# main.net
KiCad netlist of a schematic drawn in Altium Designer
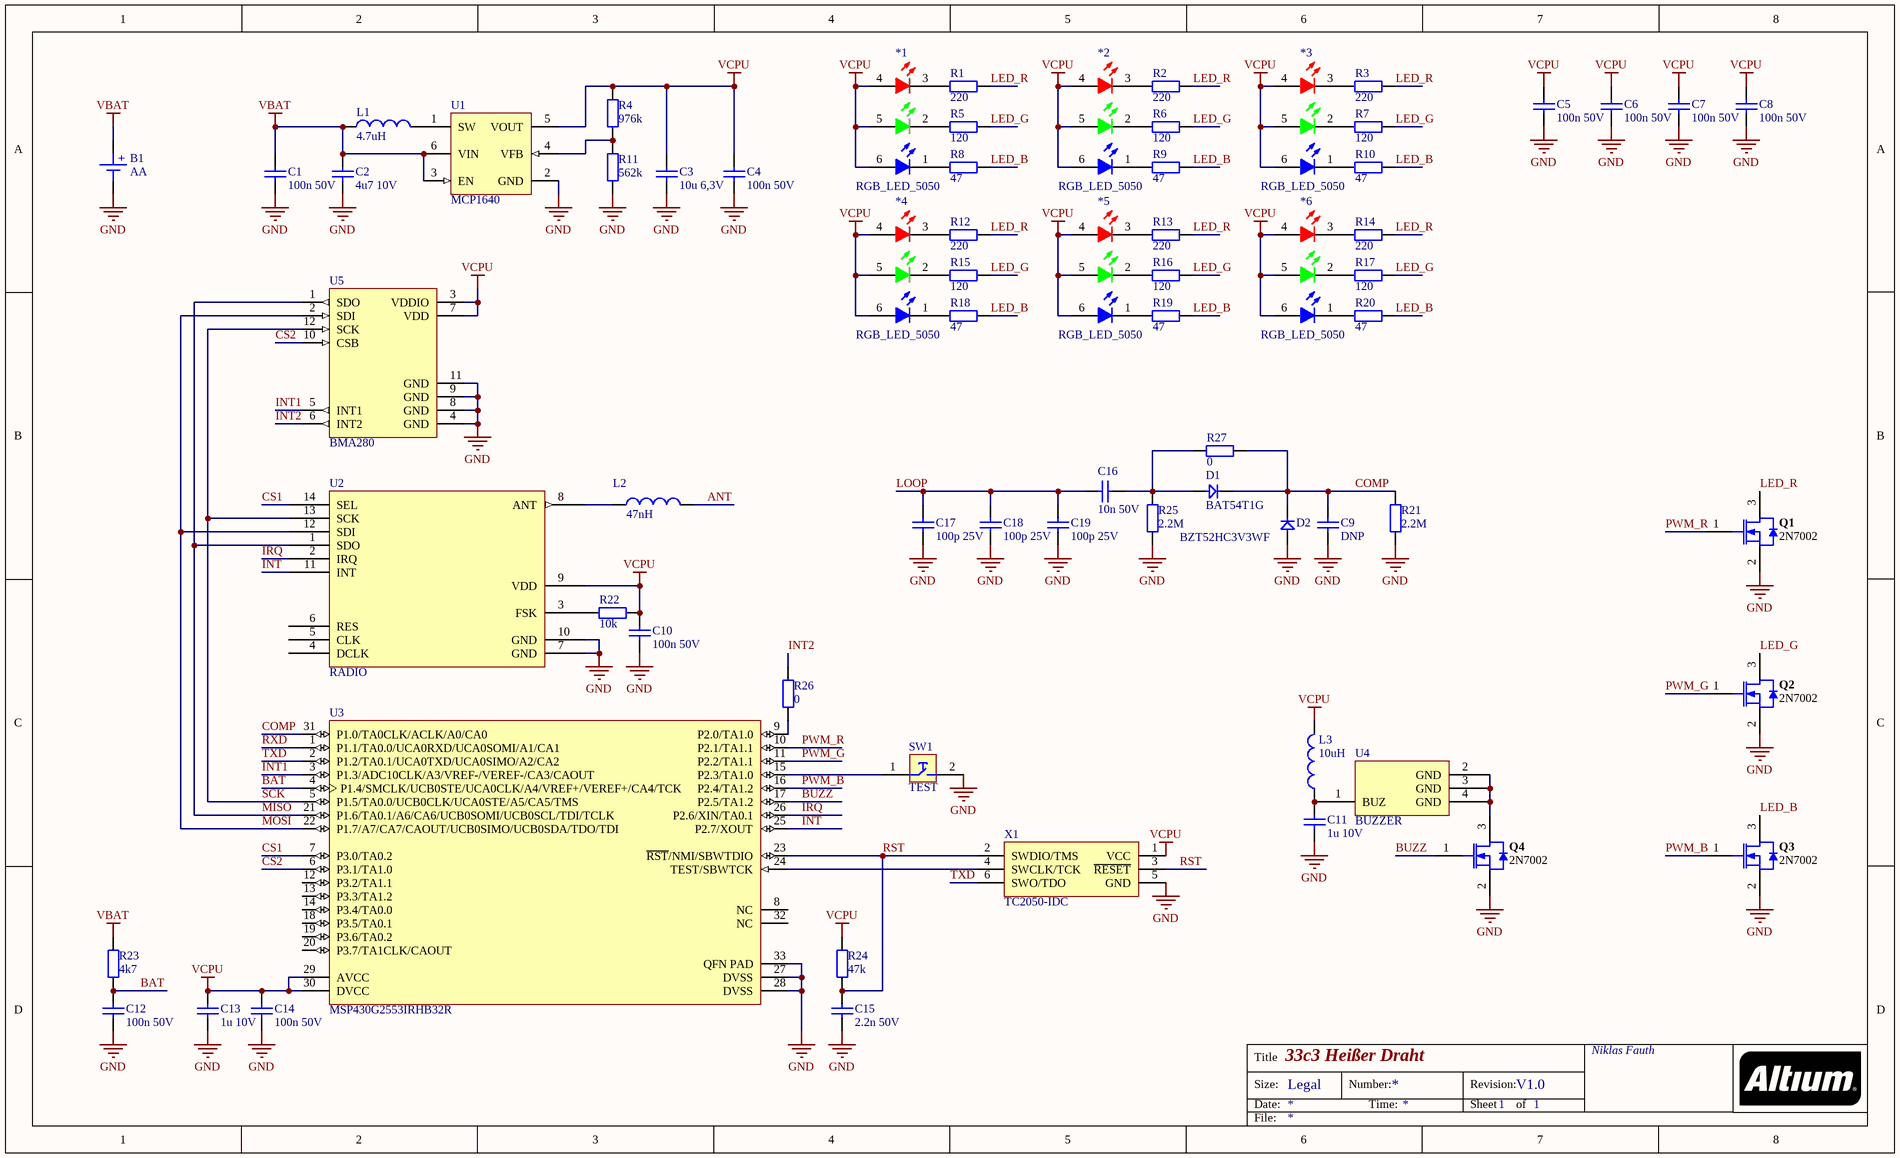
[diagram p0: main.SchDoc]

(export (version "E")
  (design (tool "Eeschema 10.0.6"))
  (components
    (comp (ref "*1")
      (value "RGB_LED_5050")
      (footprint "plcc6")
      (libsource (lib "advanced") (part "RGB_LED_5050"))
    )
    (comp (ref "*2")
      (value "RGB_LED_5050")
      (footprint "plcc6")
      (libsource (lib "advanced") (part "RGB_LED_5050"))
    )
    (comp (ref "*3")
      (value "RGB_LED_5050")
      (footprint "plcc6")
      (libsource (lib "advanced") (part "RGB_LED_5050"))
    )
    (comp (ref "*4")
      (value "RGB_LED_5050")
      (footprint "plcc6")
      (libsource (lib "advanced") (part "RGB_LED_5050"))
    )
    (comp (ref "*5")
      (value "RGB_LED_5050")
      (footprint "plcc6")
      (libsource (lib "advanced") (part "RGB_LED_5050"))
    )
    (comp (ref "*6")
      (value "RGB_LED_5050")
      (footprint "plcc6")
      (libsource (lib "advanced") (part "RGB_LED_5050"))
    )
    (comp (ref "B1")
      (value "AA")
      (footprint "AA-HOLDER")
      (description "Batt Holder AA")
      (libsource (lib "advanced") (part "AA-Batt-Holder"))
    )
    (comp (ref "C1")
      (value "100n 50V")
      (footprint "C-0603-M")
      (description "Capacitor 100n 50V")
      (libsource (lib "Passives") (part "C-0603-100n-50V"))
    )
    (comp (ref "C2")
      (value "4u7 10V")
      (footprint "C-0603-H")
      (description "Capacitor 4.7uF 10V")
      (libsource (lib "Passives") (part "C-0603-4u7-10V"))
    )
    (comp (ref "C3")
      (value "10u 6,3V")
      (footprint "C-0603-H")
      (description "Capacitor 10uF 6,3V")
      (libsource (lib "Passives") (part "C-0603-10u-6,3V"))
    )
    (comp (ref "C4")
      (value "100n 50V")
      (footprint "C-0603-M")
      (description "Capacitor 100n 50V")
      (libsource (lib "Passives") (part "C-0603-100n-50V"))
    )
    (comp (ref "C5")
      (value "100n 50V")
      (footprint "C-0603-M")
      (description "Capacitor 100n 50V")
      (libsource (lib "Passives") (part "C-0603-100n-50V"))
    )
    (comp (ref "C6")
      (value "100n 50V")
      (footprint "C-0603-M")
      (description "Capacitor 100n 50V")
      (libsource (lib "Passives") (part "C-0603-100n-50V"))
    )
    (comp (ref "C7")
      (value "100n 50V")
      (footprint "C-0603-M")
      (description "Capacitor 100n 50V")
      (libsource (lib "Passives") (part "C-0603-100n-50V"))
    )
    (comp (ref "C8")
      (value "100n 50V")
      (footprint "C-0603-M")
      (description "Capacitor 100n 50V")
      (libsource (lib "Passives") (part "C-0603-100n-50V"))
    )
    (comp (ref "C9")
      (value "DNP")
      (footprint "C-0603-H")
      (description "Capacitor 10nF 50V")
      (libsource (lib "Passives") (part "C-0603-10n-50V"))
    )
    (comp (ref "C10")
      (value "100n 50V")
      (footprint "C-0603-M")
      (description "Capacitor 100n 50V")
      (libsource (lib "Passives") (part "C-0603-100n-50V"))
    )
    (comp (ref "C11")
      (value "1u 10V")
      (footprint "C-0603-H")
      (description "Capacitor 1uF 10V")
      (libsource (lib "Passives") (part "C-0603-1u-10V"))
    )
    (comp (ref "C12")
      (value "100n 50V")
      (footprint "C-0603-M")
      (description "Capacitor 100n 50V")
      (libsource (lib "Passives") (part "C-0603-100n-50V"))
    )
    (comp (ref "C13")
      (value "1u 10V")
      (footprint "C-0603-H")
      (description "Capacitor 1uF 10V")
      (libsource (lib "Passives") (part "C-0603-1u-10V"))
    )
    (comp (ref "C14")
      (value "100n 50V")
      (footprint "C-0603-M")
      (description "Capacitor 100n 50V")
      (libsource (lib "Passives") (part "C-0603-100n-50V"))
    )
    (comp (ref "C15")
      (value "2.2n 50V")
      (footprint "C-0603-H")
      (description "Capacitor 2.2n 50V")
      (libsource (lib "Passives") (part "C-0603-2n2-50V"))
    )
    (comp (ref "C16")
      (value "10n 50V")
      (footprint "C-0603-H")
      (description "Capacitor 10nF 50V")
      (libsource (lib "Passives") (part "C-0603-10n-50V"))
    )
    (comp (ref "C17")
      (value "100p 25V")
      (footprint "C-0603-M")
      (description "Capacitor 100pF 25V")
      (libsource (lib "Passives") (part "C-0603-100p-25V"))
    )
    (comp (ref "C18")
      (value "100p 25V")
      (footprint "C-0603-M")
      (description "Capacitor 100pF 25V")
      (libsource (lib "Passives") (part "C-0603-100p-25V"))
    )
    (comp (ref "C19")
      (value "100p 25V")
      (footprint "C-0603-M")
      (description "Capacitor 100pF 25V")
      (libsource (lib "Passives") (part "C-0603-100p-25V"))
    )
    (comp (ref "D1") (value "BAT54T1G") (footprint "SOD123") (libsource (lib "advanced") (part "BAT54T1G")))
    (comp (ref "D2")
      (value "BZT52HC3V3WF")
      (footprint "SOD123")
      (description "BAT54T1G")
      (libsource (lib "advanced") (part "BAT54T1G"))
    )
    (comp (ref "L1")
      (value "4.7uH")
      (footprint "SRN4012")
      (description "SRN4012TA-4R7M")
      (libsource (lib "advanced") (part "L-SRN4012TA-4R7M"))
    )
    (comp (ref "L2") (value "47nH") (footprint "C-0603-M") (libsource (lib "advanced") (part "L-0603-47nH")))
    (comp (ref "L3")
      (value "10uH")
      (footprint "R-0805")
      (description "L 0805 10uH")
      (libsource (lib "advanced") (part "L-0805-10uH"))
    )
    (comp (ref "Q1")
      (value "2N7002")
      (footprint "INF-PG-SOT23_M")
      (fields (field (name "MANUFACTURER") "Infineon"))
      (libsource (lib "Altium Content Vault") (part "INF-NDMOS-GSD-3"))
    )
    (comp (ref "Q2")
      (value "2N7002")
      (footprint "INF-PG-SOT23_M")
      (fields (field (name "MANUFACTURER") "Infineon"))
      (libsource (lib "Altium Content Vault") (part "INF-NDMOS-GSD-3"))
    )
    (comp (ref "Q3")
      (value "2N7002")
      (footprint "INF-PG-SOT23_M")
      (fields (field (name "MANUFACTURER") "Infineon"))
      (libsource (lib "Altium Content Vault") (part "INF-NDMOS-GSD-3"))
    )
    (comp (ref "Q4")
      (value "2N7002")
      (footprint "INF-PG-SOT23_M")
      (fields (field (name "MANUFACTURER") "Infineon"))
      (libsource (lib "Altium Content Vault") (part "INF-NDMOS-GSD-3"))
    )
    (comp (ref "R1")
      (value "220")
      (footprint "R-0603-M")
      (description "Resistor 220")
      (libsource (lib "Passives") (part "R-0603-220"))
    )
    (comp (ref "R2")
      (value "220")
      (footprint "R-0603-M")
      (description "Resistor 220")
      (libsource (lib "Passives") (part "R-0603-220"))
    )
    (comp (ref "R3")
      (value "220")
      (footprint "R-0603-M")
      (description "Resistor 220")
      (libsource (lib "Passives") (part "R-0603-220"))
    )
    (comp (ref "R4")
      (value "976k")
      (footprint "R-0603-M")
      (description "Resistor 976k")
      (libsource (lib "Passives") (part "R-0603-976k"))
    )
    (comp (ref "R5")
      (value "120")
      (footprint "R-0603-M")
      (description "Resistor 120")
      (libsource (lib "Passives") (part "R-0603-120"))
    )
    (comp (ref "R6")
      (value "120")
      (footprint "R-0603-M")
      (description "Resistor 120")
      (libsource (lib "Passives") (part "R-0603-120"))
    )
    (comp (ref "R7")
      (value "120")
      (footprint "R-0603-M")
      (description "Resistor 120")
      (libsource (lib "Passives") (part "R-0603-120"))
    )
    (comp (ref "R8")
      (value "47")
      (footprint "R-0603-M")
      (description "Resistor 47")
      (libsource (lib "Passives") (part "R-0603-47"))
    )
    (comp (ref "R9")
      (value "47")
      (footprint "R-0603-M")
      (description "Resistor 47")
      (libsource (lib "Passives") (part "R-0603-47"))
    )
    (comp (ref "R10")
      (value "47")
      (footprint "R-0603-M")
      (description "Resistor 47")
      (libsource (lib "Passives") (part "R-0603-47"))
    )
    (comp (ref "R11")
      (value "562k")
      (footprint "R-0603-M")
      (description "Resistor 562k")
      (libsource (lib "Passives") (part "R-0603-562k"))
    )
    (comp (ref "R12")
      (value "220")
      (footprint "R-0603-M")
      (description "Resistor 220")
      (libsource (lib "Passives") (part "R-0603-220"))
    )
    (comp (ref "R13")
      (value "220")
      (footprint "R-0603-M")
      (description "Resistor 220")
      (libsource (lib "Passives") (part "R-0603-220"))
    )
    (comp (ref "R14")
      (value "220")
      (footprint "R-0603-M")
      (description "Resistor 220")
      (libsource (lib "Passives") (part "R-0603-220"))
    )
    (comp (ref "R15")
      (value "120")
      (footprint "R-0603-M")
      (description "Resistor 120")
      (libsource (lib "Passives") (part "R-0603-120"))
    )
    (comp (ref "R16")
      (value "120")
      (footprint "R-0603-M")
      (description "Resistor 120")
      (libsource (lib "Passives") (part "R-0603-120"))
    )
    (comp (ref "R17")
      (value "120")
      (footprint "R-0603-M")
      (description "Resistor 120")
      (libsource (lib "Passives") (part "R-0603-120"))
    )
    (comp (ref "R18")
      (value "47")
      (footprint "R-0603-M")
      (description "Resistor 47")
      (libsource (lib "Passives") (part "R-0603-47"))
    )
    (comp (ref "R19")
      (value "47")
      (footprint "R-0603-M")
      (description "Resistor 47")
      (libsource (lib "Passives") (part "R-0603-47"))
    )
    (comp (ref "R20")
      (value "47")
      (footprint "R-0603-M")
      (description "Resistor 47")
      (libsource (lib "Passives") (part "R-0603-47"))
    )
    (comp (ref "R21")
      (value "2.2M")
      (footprint "R-0603-H")
      (description "Resistor 2.2M")
      (libsource (lib "Passives") (part "R-0603-2M2"))
    )
    (comp (ref "R22")
      (value "10k")
      (footprint "R-0603-M")
      (description "Resistor 10k")
      (libsource (lib "Passives") (part "R-0603-10k"))
    )
    (comp (ref "R23")
      (value "4k7")
      (footprint "R-0603-H")
      (description "Resistor 4k7")
      (libsource (lib "Passives") (part "R-0603-4k7"))
    )
    (comp (ref "R24")
      (value "47k")
      (footprint "R-0603-H")
      (description "Resistor 4k7")
      (libsource (lib "Passives") (part "R-0603-47k"))
    )
    (comp (ref "R25")
      (value "2.2M")
      (footprint "R-0603-H")
      (description "Resistor 2.2M")
      (libsource (lib "Passives") (part "R-0603-2M2"))
    )
    (comp (ref "R26")
      (value "0")
      (footprint "R-0603-M")
      (description "Resistor 0")
      (libsource (lib "") (part "R-0603-0_1"))
    )
    (comp (ref "R27")
      (value "0")
      (footprint "R-0603-M")
      (description "Resistor 0")
      (libsource (lib "Passives") (part "R-0603-0"))
    )
    (comp (ref "SW1")
      (value "TEST")
      (footprint "switch-mini-ALPS")
      (description "SKQYAAE010")
      (libsource (lib "advanced") (part "Switch-mini-ALPS"))
    )
    (comp (ref "U1")
      (value "MCP1640")
      (footprint "SOT23-6")
      (description "aaa to 3.3V")
      (libsource (lib "advanced") (part "MCP1640"))
    )
    (comp (ref "U2")
      (value "RADIO")
      (footprint "RFM12")
      (description "Sub 1GHz Radio Module")
      (libsource (lib "advanced") (part "RFM12"))
    )
    (comp (ref "U3")
      (value "MSP430G2553IRHB32R")
      (footprint "RHB0032E_V")
      (fields (field (name "MANUFACTURER") "Texas Instruments"))
      (libsource (lib "Altium Content Vault") (part "TI-MSP430G2X53-RHB32"))
    )
    (comp (ref "U4") (value "BUZZER") (footprint "PIEZO") (libsource (lib "advanced") (part "PIEZO-1411A03")))
    (comp (ref "U5")
      (value "BMA280")
      (footprint "LGA12C50P4X4_203X203X80")
      (libsource (lib "advanced") (part "BMA280"))
    )
    (comp (ref "X1")
      (value "TC2050-IDC")
      (footprint "TC2030-IDC-NL")
      (description "TC2050-IDC SWD")
      (libsource (lib "advanced") (part "TAG-Connect-SWD"))
    )
  )
  (nets
    (net (code "1") (name "/ANT") (class "Default")
      (node (ref "L2") (pin "2") (pinfunction "2_2") (pintype "passive"))
    )
    (net (code "2") (name "/BAT") (class "Default")
      (node (ref "C12") (pin "2") (pinfunction "2_2") (pintype "passive"))
      (node (ref "R23") (pin "1") (pinfunction "1_1") (pintype "passive"))
      (node (ref "U3") (pin "4") (pinfunction "P1.4/SMCLK/UCB0STE/UCA0CLK/A4/VREF+/VEREF+/CA4/TCK_4") (pintype "bidirectional"))
    )
    (net (code "3") (name "/BUZZ") (class "Default")
      (node (ref "Q4") (pin "1") (pinfunction "GATE_1") (pintype "passive"))
      (node (ref "U3") (pin "17") (pinfunction "P2.5/TA1.2_17") (pintype "bidirectional"))
    )
    (net (code "4") (name "/COMP") (class "Default")
      (node (ref "C9") (pin "2") (pinfunction "2_2") (pintype "passive"))
      (node (ref "D1") (pin "2") (pinfunction "kt_2") (pintype "passive"))
      (node (ref "D2") (pin "2") (pinfunction "kt_2") (pintype "passive"))
      (node (ref "R21") (pin "2") (pinfunction "2_2") (pintype "passive"))
      (node (ref "R27") (pin "2") (pinfunction "2_2") (pintype "passive"))
      (node (ref "U3") (pin "31") (pinfunction "P1.0/TA0CLK/ACLK/A0/CA0_31") (pintype "bidirectional"))
    )
    (net (code "5") (name "/CS1") (class "Default")
      (node (ref "U2") (pin "14") (pinfunction "SEL_14") (pintype "passive"))
      (node (ref "U3") (pin "7") (pinfunction "P3.0/TA0.2_7") (pintype "bidirectional"))
    )
    (net (code "6") (name "/CS2") (class "Default")
      (node (ref "U3") (pin "6") (pinfunction "P3.1/TA1.0_6") (pintype "bidirectional"))
      (node (ref "U5") (pin "10") (pinfunction "CSB_10") (pintype "input"))
    )
    (net (code "7") (name "/INT") (class "Default")
      (node (ref "U2") (pin "11") (pinfunction "INT_11") (pintype "passive"))
      (node (ref "U3") (pin "25") (pinfunction "P2.7/XOUT_25") (pintype "bidirectional"))
    )
    (net (code "8") (name "/INT1") (class "Default")
      (node (ref "U3") (pin "3") (pinfunction "P1.3/ADC10CLK/A3/VREF-/VEREF-/CA3/CAOUT_3") (pintype "bidirectional"))
      (node (ref "U5") (pin "5") (pinfunction "INT1_5") (pintype "output"))
    )
    (net (code "9") (name "/INT2") (class "Default")
      (node (ref "R26") (pin "2") (pinfunction "2_2") (pintype "passive"))
      (node (ref "U5") (pin "6") (pinfunction "INT2_6") (pintype "output"))
    )
    (net (code "10") (name "/IRQ") (class "Default")
      (node (ref "U2") (pin "2") (pinfunction "IRQ_2") (pintype "passive"))
      (node (ref "U3") (pin "26") (pinfunction "P2.6/XIN/TA0.1_26") (pintype "bidirectional"))
    )
    (net (code "11") (name "/LED_B") (class "Default")
      (node (ref "Q3") (pin "3") (pinfunction "DRAIN_3") (pintype "passive"))
      (node (ref "R10") (pin "2") (pinfunction "2_2") (pintype "passive"))
      (node (ref "R18") (pin "2") (pinfunction "2_2") (pintype "passive"))
      (node (ref "R19") (pin "2") (pinfunction "2_2") (pintype "passive"))
      (node (ref "R20") (pin "2") (pinfunction "2_2") (pintype "passive"))
      (node (ref "R8") (pin "2") (pinfunction "2_2") (pintype "passive"))
      (node (ref "R9") (pin "2") (pinfunction "2_2") (pintype "passive"))
    )
    (net (code "12") (name "/LED_G") (class "Default")
      (node (ref "Q2") (pin "3") (pinfunction "DRAIN_3") (pintype "passive"))
      (node (ref "R15") (pin "2") (pinfunction "2_2") (pintype "passive"))
      (node (ref "R16") (pin "2") (pinfunction "2_2") (pintype "passive"))
      (node (ref "R17") (pin "2") (pinfunction "2_2") (pintype "passive"))
      (node (ref "R5") (pin "2") (pinfunction "2_2") (pintype "passive"))
      (node (ref "R6") (pin "2") (pinfunction "2_2") (pintype "passive"))
      (node (ref "R7") (pin "2") (pinfunction "2_2") (pintype "passive"))
    )
    (net (code "13") (name "/LED_R") (class "Default")
      (node (ref "Q1") (pin "3") (pinfunction "DRAIN_3") (pintype "passive"))
      (node (ref "R1") (pin "2") (pinfunction "2_2") (pintype "passive"))
      (node (ref "R12") (pin "2") (pinfunction "2_2") (pintype "passive"))
      (node (ref "R13") (pin "2") (pinfunction "2_2") (pintype "passive"))
      (node (ref "R14") (pin "2") (pinfunction "2_2") (pintype "passive"))
      (node (ref "R2") (pin "2") (pinfunction "2_2") (pintype "passive"))
      (node (ref "R3") (pin "2") (pinfunction "2_2") (pintype "passive"))
    )
    (net (code "14") (name "/LOOP") (class "Default")
      (node (ref "C16") (pin "1") (pinfunction "1_1") (pintype "passive"))
      (node (ref "C17") (pin "2") (pinfunction "2_2") (pintype "passive"))
      (node (ref "C18") (pin "2") (pinfunction "2_2") (pintype "passive"))
      (node (ref "C19") (pin "2") (pinfunction "2_2") (pintype "passive"))
    )
    (net (code "15") (name "/MISO") (class "Default")
      (node (ref "U2") (pin "1") (pinfunction "SDO_1") (pintype "passive"))
      (node (ref "U3") (pin "21") (pinfunction "P1.6/TA0.1/A6/CA6/UCB0SOMI/UCB0SCL/TDI/TCLK_21") (pintype "bidirectional"))
      (node (ref "U5") (pin "1") (pinfunction "SDO_1") (pintype "output"))
    )
    (net (code "16") (name "/MOSI") (class "Default")
      (node (ref "U2") (pin "12") (pinfunction "SDI_12") (pintype "passive"))
      (node (ref "U3") (pin "22") (pinfunction "P1.7/A7/CA7/CAOUT/UCB0SIMO/UCB0SDA/TDO/TDI_22") (pintype "bidirectional"))
      (node (ref "U5") (pin "2") (pinfunction "SDI_2") (pintype "input"))
    )
    (net (code "17") (name "/PWM_B") (class "Default")
      (node (ref "Q3") (pin "1") (pinfunction "GATE_1") (pintype "passive"))
      (node (ref "U3") (pin "16") (pinfunction "P2.4/TA1.2_16") (pintype "bidirectional"))
    )
    (net (code "18") (name "/PWM_G") (class "Default")
      (node (ref "Q2") (pin "1") (pinfunction "GATE_1") (pintype "passive"))
      (node (ref "U3") (pin "11") (pinfunction "P2.2/TA1.1_11") (pintype "bidirectional"))
    )
    (net (code "19") (name "/PWM_R") (class "Default")
      (node (ref "Q1") (pin "1") (pinfunction "GATE_1") (pintype "passive"))
      (node (ref "U3") (pin "10") (pinfunction "P2.1/TA1.1_10") (pintype "bidirectional"))
    )
    (net (code "20") (name "/RST") (class "Default")
      (node (ref "C15") (pin "2") (pinfunction "2_2") (pintype "passive"))
      (node (ref "R24") (pin "1") (pinfunction "1_1") (pintype "passive"))
      (node (ref "U3") (pin "23") (pinfunction "~{RST}/NMI/SBWTDIO_23") (pintype "bidirectional"))
      (node (ref "X1") (pin "2") (pinfunction "SWDIO/TMS_2") (pintype "passive"))
      (node (ref "X1") (pin "3") (pinfunction "~{RESET}_3") (pintype "passive"))
    )
    (net (code "21") (name "/RXD") (class "Default")
      (node (ref "U3") (pin "1") (pinfunction "P1.1/TA0.0/UCA0RXD/UCA0SOMI/A1/CA1_1") (pintype "bidirectional"))
    )
    (net (code "22") (name "/SCK") (class "Default")
      (node (ref "U2") (pin "13") (pinfunction "SCK_13") (pintype "passive"))
      (node (ref "U3") (pin "5") (pinfunction "P1.5/TA0.0/UCB0CLK/UCA0STE/A5/CA5/TMS_5") (pintype "bidirectional"))
      (node (ref "U5") (pin "12") (pinfunction "SCK_12") (pintype "input"))
    )
    (net (code "23") (name "/TXD") (class "Default")
      (node (ref "U3") (pin "2") (pinfunction "P1.2/TA0.1/UCA0TXD/UCA0SIMO/A2/CA2_2") (pintype "bidirectional"))
      (node (ref "X1") (pin "6") (pinfunction "SWO/TDO_6") (pintype "passive"))
    )
    (net (code "24") (name "GND") (class "Default")
      (node (ref "B1") (pin "1") (pintype "passive"))
      (node (ref "C1") (pin "1") (pinfunction "1_1") (pintype "passive"))
      (node (ref "C10") (pin "1") (pinfunction "1_1") (pintype "passive"))
      (node (ref "C11") (pin "1") (pinfunction "1_1") (pintype "passive"))
      (node (ref "C12") (pin "1") (pinfunction "1_1") (pintype "passive"))
      (node (ref "C13") (pin "1") (pinfunction "1_1") (pintype "passive"))
      (node (ref "C14") (pin "1") (pinfunction "1_1") (pintype "passive"))
      (node (ref "C15") (pin "1") (pinfunction "1_1") (pintype "passive"))
      (node (ref "C17") (pin "1") (pinfunction "1_1") (pintype "passive"))
      (node (ref "C18") (pin "1") (pinfunction "1_1") (pintype "passive"))
      (node (ref "C19") (pin "1") (pinfunction "1_1") (pintype "passive"))
      (node (ref "C2") (pin "1") (pinfunction "1_1") (pintype "passive"))
      (node (ref "C3") (pin "1") (pinfunction "1_1") (pintype "passive"))
      (node (ref "C4") (pin "1") (pinfunction "1_1") (pintype "passive"))
      (node (ref "C5") (pin "1") (pinfunction "1_1") (pintype "passive"))
      (node (ref "C6") (pin "1") (pinfunction "1_1") (pintype "passive"))
      (node (ref "C7") (pin "1") (pinfunction "1_1") (pintype "passive"))
      (node (ref "C8") (pin "1") (pinfunction "1_1") (pintype "passive"))
      (node (ref "C9") (pin "1") (pinfunction "1_1") (pintype "passive"))
      (node (ref "D2") (pin "1") (pinfunction "an_1") (pintype "passive"))
      (node (ref "Q1") (pin "2") (pinfunction "SOURCE_2") (pintype "passive"))
      (node (ref "Q2") (pin "2") (pinfunction "SOURCE_2") (pintype "passive"))
      (node (ref "Q3") (pin "2") (pinfunction "SOURCE_2") (pintype "passive"))
      (node (ref "Q4") (pin "2") (pinfunction "SOURCE_2") (pintype "passive"))
      (node (ref "R11") (pin "1") (pinfunction "1_1") (pintype "passive"))
      (node (ref "R21") (pin "1") (pinfunction "1_1") (pintype "passive"))
      (node (ref "R25") (pin "1") (pinfunction "1_1") (pintype "passive"))
      (node (ref "SW1") (pin "2") (pintype "passive"))
      (node (ref "U1") (pin "2") (pinfunction "GND_2") (pintype "power_in"))
      (node (ref "U2") (pin "10") (pinfunction "GND_10") (pintype "passive"))
      (node (ref "U2") (pin "7") (pinfunction "GND_7") (pintype "passive"))
      (node (ref "U3") (pin "27") (pinfunction "DVSS_27") (pintype "power_in"))
      (node (ref "U3") (pin "28") (pinfunction "DVSS_28") (pintype "power_in"))
      (node (ref "U3") (pin "33") (pinfunction "QFN_PAD_33") (pintype "power_in"))
      (node (ref "U5") (pin "11") (pinfunction "GND_11") (pintype "power_in"))
      (node (ref "U5") (pin "4") (pinfunction "GND_4") (pintype "power_in"))
      (node (ref "U5") (pin "8") (pinfunction "GND_8") (pintype "power_in"))
      (node (ref "U5") (pin "9") (pinfunction "GND_9") (pintype "power_in"))
      (node (ref "X1") (pin "5") (pinfunction "GND_5") (pintype "passive"))
    )
    (net (code "25") (name "Net-(*1-K-Pad1)") (class "Default")
      (node (ref "*1") (pin "1") (pinfunction "K_1") (pintype "passive"))
      (node (ref "R8") (pin "1") (pinfunction "1_1") (pintype "passive"))
    )
    (net (code "26") (name "Net-(*1-K-Pad2)") (class "Default")
      (node (ref "*1") (pin "2") (pinfunction "K_2") (pintype "passive"))
      (node (ref "R5") (pin "1") (pinfunction "1_1") (pintype "passive"))
    )
    (net (code "27") (name "Net-(*1-K-Pad3)") (class "Default")
      (node (ref "*1") (pin "3") (pinfunction "K_3") (pintype "passive"))
      (node (ref "R1") (pin "1") (pinfunction "1_1") (pintype "passive"))
    )
    (net (code "28") (name "Net-(*2-K-Pad1)") (class "Default")
      (node (ref "*2") (pin "1") (pinfunction "K_1") (pintype "passive"))
      (node (ref "R9") (pin "1") (pinfunction "1_1") (pintype "passive"))
    )
    (net (code "29") (name "Net-(*2-K-Pad2)") (class "Default")
      (node (ref "*2") (pin "2") (pinfunction "K_2") (pintype "passive"))
      (node (ref "R6") (pin "1") (pinfunction "1_1") (pintype "passive"))
    )
    (net (code "30") (name "Net-(*2-K-Pad3)") (class "Default")
      (node (ref "*2") (pin "3") (pinfunction "K_3") (pintype "passive"))
      (node (ref "R2") (pin "1") (pinfunction "1_1") (pintype "passive"))
    )
    (net (code "31") (name "Net-(*3-K-Pad1)") (class "Default")
      (node (ref "*3") (pin "1") (pinfunction "K_1") (pintype "passive"))
      (node (ref "R10") (pin "1") (pinfunction "1_1") (pintype "passive"))
    )
    (net (code "32") (name "Net-(*3-K-Pad2)") (class "Default")
      (node (ref "*3") (pin "2") (pinfunction "K_2") (pintype "passive"))
      (node (ref "R7") (pin "1") (pinfunction "1_1") (pintype "passive"))
    )
    (net (code "33") (name "Net-(*3-K-Pad3)") (class "Default")
      (node (ref "*3") (pin "3") (pinfunction "K_3") (pintype "passive"))
      (node (ref "R3") (pin "1") (pinfunction "1_1") (pintype "passive"))
    )
    (net (code "34") (name "Net-(*4-K-Pad1)") (class "Default")
      (node (ref "*4") (pin "1") (pinfunction "K_1") (pintype "passive"))
      (node (ref "R18") (pin "1") (pinfunction "1_1") (pintype "passive"))
    )
    (net (code "35") (name "Net-(*4-K-Pad2)") (class "Default")
      (node (ref "*4") (pin "2") (pinfunction "K_2") (pintype "passive"))
      (node (ref "R15") (pin "1") (pinfunction "1_1") (pintype "passive"))
    )
    (net (code "36") (name "Net-(*4-K-Pad3)") (class "Default")
      (node (ref "*4") (pin "3") (pinfunction "K_3") (pintype "passive"))
      (node (ref "R12") (pin "1") (pinfunction "1_1") (pintype "passive"))
    )
    (net (code "37") (name "Net-(*5-K-Pad1)") (class "Default")
      (node (ref "*5") (pin "1") (pinfunction "K_1") (pintype "passive"))
      (node (ref "R19") (pin "1") (pinfunction "1_1") (pintype "passive"))
    )
    (net (code "38") (name "Net-(*5-K-Pad2)") (class "Default")
      (node (ref "*5") (pin "2") (pinfunction "K_2") (pintype "passive"))
      (node (ref "R16") (pin "1") (pinfunction "1_1") (pintype "passive"))
    )
    (net (code "39") (name "Net-(*5-K-Pad3)") (class "Default")
      (node (ref "*5") (pin "3") (pinfunction "K_3") (pintype "passive"))
      (node (ref "R13") (pin "1") (pinfunction "1_1") (pintype "passive"))
    )
    (net (code "40") (name "Net-(*6-K-Pad1)") (class "Default")
      (node (ref "*6") (pin "1") (pinfunction "K_1") (pintype "passive"))
      (node (ref "R20") (pin "1") (pinfunction "1_1") (pintype "passive"))
    )
    (net (code "41") (name "Net-(*6-K-Pad2)") (class "Default")
      (node (ref "*6") (pin "2") (pinfunction "K_2") (pintype "passive"))
      (node (ref "R17") (pin "1") (pinfunction "1_1") (pintype "passive"))
    )
    (net (code "42") (name "Net-(*6-K-Pad3)") (class "Default")
      (node (ref "*6") (pin "3") (pinfunction "K_3") (pintype "passive"))
      (node (ref "R14") (pin "1") (pinfunction "1_1") (pintype "passive"))
    )
    (net (code "43") (name "Net-(D1-an)") (class "Default")
      (node (ref "C16") (pin "2") (pinfunction "2_2") (pintype "passive"))
      (node (ref "D1") (pin "1") (pinfunction "an_1") (pintype "passive"))
      (node (ref "R25") (pin "2") (pinfunction "2_2") (pintype "passive"))
      (node (ref "R27") (pin "1") (pinfunction "1_1") (pintype "passive"))
    )
    (net (code "44") (name "Net-(Q4-DRAIN)") (class "Default")
      (node (ref "Q4") (pin "3") (pinfunction "DRAIN_3") (pintype "passive"))
      (node (ref "U4") (pin "2") (pinfunction "GND_2") (pintype "passive"))
      (node (ref "U4") (pin "3") (pinfunction "GND_3") (pintype "passive"))
      (node (ref "U4") (pin "4") (pinfunction "GND_4") (pintype "passive"))
    )
    (net (code "45") (name "Net-(U1-SW)") (class "Default")
      (node (ref "L1") (pin "2") (pinfunction "2_2") (pintype "passive"))
      (node (ref "U1") (pin "1") (pinfunction "SW_1") (pintype "passive"))
    )
    (net (code "46") (name "Net-(U1-VFB)") (class "Default")
      (node (ref "R11") (pin "2") (pinfunction "2_2") (pintype "passive"))
      (node (ref "R4") (pin "1") (pinfunction "1_1") (pintype "passive"))
      (node (ref "U1") (pin "4") (pinfunction "VFB_4") (pintype "input"))
    )
    (net (code "47") (name "Net-(U2-ANT)") (class "Default")
      (node (ref "L2") (pin "1") (pinfunction "1_1") (pintype "passive"))
      (node (ref "U2") (pin "8") (pinfunction "ANT_8") (pintype "output"))
    )
    (net (code "48") (name "Net-(U2-FSK)") (class "Default")
      (node (ref "R22") (pin "1") (pinfunction "1_1") (pintype "passive"))
      (node (ref "U2") (pin "3") (pinfunction "FSK_3") (pintype "passive"))
    )
    (net (code "49") (name "Net-(U3-P2.0{slash}TA1.0)") (class "Default")
      (node (ref "R26") (pin "1") (pinfunction "1_1") (pintype "passive"))
      (node (ref "U3") (pin "9") (pinfunction "P2.0/TA1.0_9") (pintype "bidirectional"))
    )
    (net (code "50") (name "Net-(U3-P2.3{slash}TA1.0)") (class "Default")
      (node (ref "SW1") (pin "1") (pintype "passive"))
      (node (ref "U3") (pin "15") (pinfunction "P2.3/TA1.0_15") (pintype "bidirectional"))
    )
    (net (code "51") (name "Net-(U3-TEST{slash}SBWTCK)") (class "Default")
      (node (ref "U3") (pin "24") (pinfunction "TEST/SBWTCK_24") (pintype "input"))
      (node (ref "X1") (pin "4") (pinfunction "SWCLK/TCK_4") (pintype "passive"))
    )
    (net (code "52") (name "Net-(U4-BUZ)") (class "Default")
      (node (ref "C11") (pin "2") (pinfunction "2_2") (pintype "passive"))
      (node (ref "L3") (pin "1") (pinfunction "1_1") (pintype "passive"))
      (node (ref "U4") (pin "1") (pinfunction "BUZ_1") (pintype "passive"))
    )
    (net (code "53") (name "VBAT") (class "Default")
      (node (ref "B1") (pin "2") (pintype "passive"))
      (node (ref "C1") (pin "2") (pinfunction "2_2") (pintype "passive"))
      (node (ref "C2") (pin "2") (pinfunction "2_2") (pintype "passive"))
      (node (ref "L1") (pin "1") (pinfunction "1_1") (pintype "passive"))
      (node (ref "R23") (pin "2") (pinfunction "2_2") (pintype "passive"))
      (node (ref "U1") (pin "3") (pinfunction "EN_3") (pintype "input"))
      (node (ref "U1") (pin "6") (pinfunction "VIN_6") (pintype "power_in"))
    )
    (net (code "54") (name "VCPU") (class "Default")
      (node (ref "*1") (pin "4") (pinfunction "A_4") (pintype "passive"))
      (node (ref "*1") (pin "5") (pinfunction "A_5") (pintype "passive"))
      (node (ref "*1") (pin "6") (pinfunction "A_6") (pintype "passive"))
      (node (ref "*2") (pin "4") (pinfunction "A_4") (pintype "passive"))
      (node (ref "*2") (pin "5") (pinfunction "A_5") (pintype "passive"))
      (node (ref "*2") (pin "6") (pinfunction "A_6") (pintype "passive"))
      (node (ref "*3") (pin "4") (pinfunction "A_4") (pintype "passive"))
      (node (ref "*3") (pin "5") (pinfunction "A_5") (pintype "passive"))
      (node (ref "*3") (pin "6") (pinfunction "A_6") (pintype "passive"))
      (node (ref "*4") (pin "4") (pinfunction "A_4") (pintype "passive"))
      (node (ref "*4") (pin "5") (pinfunction "A_5") (pintype "passive"))
      (node (ref "*4") (pin "6") (pinfunction "A_6") (pintype "passive"))
      (node (ref "*5") (pin "4") (pinfunction "A_4") (pintype "passive"))
      (node (ref "*5") (pin "5") (pinfunction "A_5") (pintype "passive"))
      (node (ref "*5") (pin "6") (pinfunction "A_6") (pintype "passive"))
      (node (ref "*6") (pin "4") (pinfunction "A_4") (pintype "passive"))
      (node (ref "*6") (pin "5") (pinfunction "A_5") (pintype "passive"))
      (node (ref "*6") (pin "6") (pinfunction "A_6") (pintype "passive"))
      (node (ref "C10") (pin "2") (pinfunction "2_2") (pintype "passive"))
      (node (ref "C13") (pin "2") (pinfunction "2_2") (pintype "passive"))
      (node (ref "C14") (pin "2") (pinfunction "2_2") (pintype "passive"))
      (node (ref "C3") (pin "2") (pinfunction "2_2") (pintype "passive"))
      (node (ref "C4") (pin "2") (pinfunction "2_2") (pintype "passive"))
      (node (ref "C5") (pin "2") (pinfunction "2_2") (pintype "passive"))
      (node (ref "C6") (pin "2") (pinfunction "2_2") (pintype "passive"))
      (node (ref "C7") (pin "2") (pinfunction "2_2") (pintype "passive"))
      (node (ref "C8") (pin "2") (pinfunction "2_2") (pintype "passive"))
      (node (ref "L3") (pin "2") (pinfunction "2_2") (pintype "passive"))
      (node (ref "R22") (pin "2") (pinfunction "2_2") (pintype "passive"))
      (node (ref "R24") (pin "2") (pinfunction "2_2") (pintype "passive"))
      (node (ref "R4") (pin "2") (pinfunction "2_2") (pintype "passive"))
      (node (ref "U1") (pin "5") (pinfunction "VOUT_5") (pintype "power_in"))
      (node (ref "U2") (pin "9") (pinfunction "VDD_9") (pintype "passive"))
      (node (ref "U3") (pin "29") (pinfunction "AVCC_29") (pintype "power_in"))
      (node (ref "U3") (pin "30") (pinfunction "DVCC_30") (pintype "power_in"))
      (node (ref "U5") (pin "3") (pinfunction "VDDIO_3") (pintype "power_in"))
      (node (ref "U5") (pin "7") (pinfunction "VDD_7") (pintype "power_in"))
      (node (ref "X1") (pin "1") (pinfunction "VCC_1") (pintype "passive"))
    )
    (net (code "55") (name "unconnected-(U2-CLK-Pad5)") (class "Default")
      (node (ref "U2") (pin "5") (pinfunction "CLK_5") (pintype "passive"))
    )
    (net (code "56") (name "unconnected-(U2-DCLK-Pad4)") (class "Default")
      (node (ref "U2") (pin "4") (pinfunction "DCLK_4") (pintype "passive"))
    )
    (net (code "57") (name "unconnected-(U2-RES-Pad6)") (class "Default")
      (node (ref "U2") (pin "6") (pinfunction "RES_6") (pintype "passive"))
    )
    (net (code "58") (name "unconnected-(U3-NC-Pad8)") (class "Default")
      (node (ref "U3") (pin "8") (pinfunction "NC_8") (pintype "passive"))
    )
    (net (code "59") (name "unconnected-(U3-NC-Pad32)") (class "Default")
      (node (ref "U3") (pin "32") (pinfunction "NC_32") (pintype "passive"))
    )
    (net (code "60") (name "unconnected-(U3-P3.2{slash}TA1.1-Pad12)") (class "Default")
      (node (ref "U3") (pin "12") (pinfunction "P3.2/TA1.1_12") (pintype "bidirectional"))
    )
    (net (code "61") (name "unconnected-(U3-P3.3{slash}TA1.2-Pad13)") (class "Default")
      (node (ref "U3") (pin "13") (pinfunction "P3.3/TA1.2_13") (pintype "bidirectional"))
    )
    (net (code "62") (name "unconnected-(U3-P3.4{slash}TA0.0-Pad14)") (class "Default")
      (node (ref "U3") (pin "14") (pinfunction "P3.4/TA0.0_14") (pintype "bidirectional"))
    )
    (net (code "63") (name "unconnected-(U3-P3.5{slash}TA0.1-Pad18)") (class "Default")
      (node (ref "U3") (pin "18") (pinfunction "P3.5/TA0.1_18") (pintype "bidirectional"))
    )
    (net (code "64") (name "unconnected-(U3-P3.6{slash}TA0.2-Pad19)") (class "Default")
      (node (ref "U3") (pin "19") (pinfunction "P3.6/TA0.2_19") (pintype "bidirectional"))
    )
    (net (code "65") (name "unconnected-(U3-P3.7{slash}TA1CLK{slash}CAOUT-Pad20)") (class "Default")
      (node (ref "U3") (pin "20") (pinfunction "P3.7/TA1CLK/CAOUT_20") (pintype "bidirectional"))
    )
  )
)
